# USB-PS2_1.net
KiCad netlist of a schematic drawn in Altium Designer
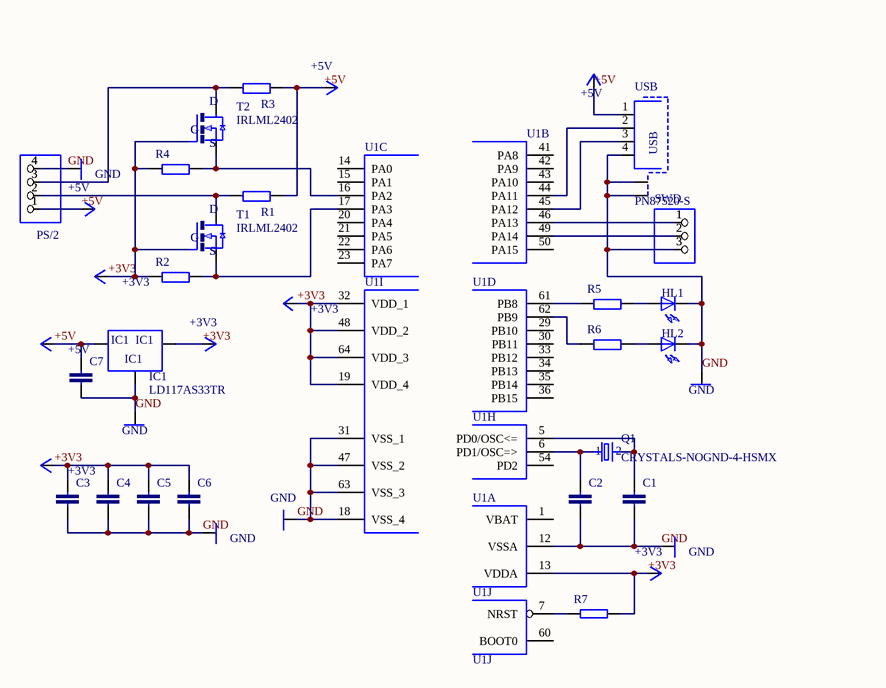
[diagram p0: USB-PS2_1.SchDoc]

(export (version "E")
  (design (tool "Eeschema 10.0.6"))
  (components
    (comp (ref "+3V1") (value "+3V3") (libsource (lib "supply1") (part "+3V3")))
    (comp (ref "+3V2") (value "+3V3") (libsource (lib "supply1") (part "+3V3")))
    (comp (ref "+3V3") (value "+3V3") (libsource (lib "") (part "+3V3_1")))
    (comp (ref "+3V4") (value "+3V3") (libsource (lib "supply1") (part "+3V3")))
    (comp (ref "+3V5") (value "+3V3") (libsource (lib "supply1") (part "+3V3")))
    (comp (ref "C1") (value "~") (footprint "C0603K") (libsource (lib "rcl") (part "C-EUC0603K")))
    (comp (ref "C2") (value "~") (footprint "C0603K") (libsource (lib "rcl") (part "C-EUC0603K")))
    (comp (ref "C3") (value "~") (footprint "C0603K") (libsource (lib "rcl") (part "C-EUC0603K")))
    (comp (ref "C4") (value "~") (footprint "C0603K") (libsource (lib "rcl") (part "C-EUC0603K")))
    (comp (ref "C5") (value "~") (footprint "C0603K") (libsource (lib "rcl") (part "C-EUC0603K")))
    (comp (ref "C6") (value "~") (footprint "C0603K") (libsource (lib "rcl") (part "C-EUC0603K")))
    (comp (ref "C7") (value "~") (footprint "C0603K") (libsource (lib "rcl") (part "C-EUC0603K")))
    (comp (ref "GND1") (value "GND") (libsource (lib "supply1") (part "GND")))
    (comp (ref "GND3") (value "GND") (libsource (lib "") (part "GND_1")))
    (comp (ref "GND4") (value "GND") (libsource (lib "supply1") (part "GND")))
    (comp (ref "GND5") (value "GND") (libsource (lib "supply1") (part "GND")))
    (comp (ref "GND6") (value "GND") (libsource (lib "supply1") (part "GND")))
    (comp (ref "GND7") (value "GND") (libsource (lib "supply1") (part "GND")))
    (comp (ref "HL1") (value "~") (footprint "SML0805") (libsource (lib "led") (part "LEDSML0805")))
    (comp (ref "HL2") (value "~") (footprint "SML0805") (libsource (lib "led") (part "LEDSML0805")))
    (comp (ref "IC1")
      (value "LD117AS33TR")
      (footprint "SOT223")
      (libsource (lib "v-reg") (part "LD117AS33TR"))
    )
    (comp (ref "P+1") (value "+5V") (libsource (lib "") (part "+5V_1")))
    (comp (ref "P+2") (value "+5V") (libsource (lib "") (part "+5V_1")))
    (comp (ref "P+3") (value "+5V") (libsource (lib "") (part "+5V_1")))
    (comp (ref "P+4") (value "+5V") (libsource (lib "supply1") (part "+5V")))
    (comp (ref "PS/2") (value "~") (footprint "1X04") (libsource (lib "pinhead") (part "PINHD-1X4")))
    (comp (ref "Q1")
      (value "CRYSTALS-NOGND-4-HSMX")
      (footprint "HC49-4-HSMX")
      (libsource (lib "IQD-Frequency-Products") (part "CRYSTALS-NOGND-4-HSMX"))
    )
    (comp (ref "R1") (value "~") (footprint "R0603") (libsource (lib "") (part "R-EU_R0603_2")))
    (comp (ref "R2") (value "~") (footprint "R0603") (libsource (lib "rcl") (part "R-EU_R0603")))
    (comp (ref "R3") (value "~") (footprint "R0603") (libsource (lib "") (part "R-EU_R0603_2")))
    (comp (ref "R4") (value "~") (footprint "R0603") (libsource (lib "rcl") (part "R-EU_R0603")))
    (comp (ref "R5") (value "~") (footprint "R0603") (libsource (lib "rcl") (part "R-EU_R0603")))
    (comp (ref "R6") (value "~") (footprint "R0603") (libsource (lib "rcl") (part "R-EU_R0603")))
    (comp (ref "R7") (value "~") (footprint "R0603") (libsource (lib "") (part "R-EU_R0603_1")))
    (comp (ref "SWD") (value "~") (footprint "1X03") (libsource (lib "pinhead") (part "PINHD-1X3")))
    (comp (ref "T1")
      (value "IRLML2402")
      (footprint "MICRO3")
      (libsource (lib "transistor-power") (part "IRLML2402"))
    )
    (comp (ref "T2")
      (value "IRLML2402")
      (footprint "MICRO3")
      (libsource (lib "transistor-power") (part "IRLML2402"))
    )
    (comp (ref "U1") (value "~") (footprint "TQFP64") (libsource (lib "") (part "STM32F10XRXT6_2")))
    (comp (ref "USB")
      (value "PN87520-S")
      (footprint "PN87520-S")
      (libsource (lib "con-berg") (part "PN87520-S"))
    )
  )
  (nets
    (net (code "1") (name "/+3V3") (class "Default")
      (node (ref "+3V1") (pin "0") (pinfunction "+3V3_0") (pintype "passive"))
      (node (ref "+3V2") (pin "0") (pinfunction "+3V3_0") (pintype "passive"))
      (node (ref "+3V3") (pin "0") (pinfunction "+3V3_0") (pintype "passive"))
      (node (ref "+3V4") (pin "0") (pinfunction "+3V3_0") (pintype "passive"))
      (node (ref "+3V5") (pin "0") (pinfunction "+3V3_0") (pintype "passive"))
      (node (ref "C3") (pin "1") (pinfunction "1_1") (pintype "passive"))
      (node (ref "C4") (pin "1") (pinfunction "1_1") (pintype "passive"))
      (node (ref "C5") (pin "1") (pinfunction "1_1") (pintype "passive"))
      (node (ref "C6") (pin "1") (pinfunction "1_1") (pintype "passive"))
      (node (ref "IC1") (pin "4") (pinfunction "OUT_4") (pintype "passive"))
      (node (ref "R2") (pin "1") (pinfunction "1_1") (pintype "passive"))
      (node (ref "R4") (pin "1") (pinfunction "1_1") (pintype "passive"))
      (node (ref "R7") (pin "2") (pinfunction "2_2") (pintype "passive"))
      (node (ref "T1") (pin "1") (pinfunction "G_1") (pintype "passive"))
      (node (ref "T2") (pin "1") (pinfunction "G_1") (pintype "passive"))
      (node (ref "U1") (pin "13") (pinfunction "VDDA_13") (pintype "passive"))
      (node (ref "U1") (pin "19") (pinfunction "VDD_4_19") (pintype "passive"))
      (node (ref "U1") (pin "32") (pinfunction "VDD_1_32") (pintype "passive"))
      (node (ref "U1") (pin "48") (pinfunction "VDD_2_48") (pintype "passive"))
      (node (ref "U1") (pin "64") (pinfunction "VDD_3_64") (pintype "passive"))
    )
    (net (code "2") (name "/+5V") (class "Default")
      (node (ref "C7") (pin "1") (pinfunction "1_1") (pintype "passive"))
      (node (ref "IC1") (pin "3") (pinfunction "IN_3") (pintype "passive"))
      (node (ref "P+1") (pin "0") (pinfunction "+5V_0") (pintype "passive"))
      (node (ref "P+2") (pin "0") (pinfunction "+5V_0") (pintype "passive"))
      (node (ref "P+3") (pin "0") (pinfunction "+5V_0") (pintype "passive"))
      (node (ref "P+4") (pin "0") (pinfunction "+5V_0") (pintype "passive"))
      (node (ref "PS/2") (pin "1") (pinfunction "1_1") (pintype "passive"))
      (node (ref "R1") (pin "1") (pinfunction "1_1") (pintype "passive"))
      (node (ref "R3") (pin "1") (pinfunction "1_1") (pintype "passive"))
      (node (ref "USB") (pin "1") (pinfunction "1_1") (pintype "passive"))
    )
    (net (code "3") (name "/GND") (class "Default")
      (node (ref "C1") (pin "2") (pinfunction "2_2") (pintype "passive"))
      (node (ref "C2") (pin "2") (pinfunction "2_2") (pintype "passive"))
      (node (ref "C3") (pin "2") (pinfunction "2_2") (pintype "passive"))
      (node (ref "C4") (pin "2") (pinfunction "2_2") (pintype "passive"))
      (node (ref "C5") (pin "2") (pinfunction "2_2") (pintype "passive"))
      (node (ref "C6") (pin "2") (pinfunction "2_2") (pintype "passive"))
      (node (ref "C7") (pin "2") (pinfunction "2_2") (pintype "passive"))
      (node (ref "GND1") (pin "0") (pinfunction "GND_0") (pintype "passive"))
      (node (ref "GND3") (pin "0") (pinfunction "GND_0") (pintype "passive"))
      (node (ref "GND4") (pin "0") (pinfunction "GND_0") (pintype "passive"))
      (node (ref "GND5") (pin "0") (pinfunction "GND_0") (pintype "passive"))
      (node (ref "GND6") (pin "0") (pinfunction "GND_0") (pintype "passive"))
      (node (ref "GND7") (pin "0") (pinfunction "GND_0") (pintype "passive"))
      (node (ref "HL1") (pin "C") (pinfunction "C_C") (pintype "passive"))
      (node (ref "HL2") (pin "C") (pinfunction "C_C") (pintype "passive"))
      (node (ref "IC1") (pin "1") (pinfunction "ADJ_1") (pintype "passive"))
      (node (ref "PS/2") (pin "4") (pinfunction "4_4") (pintype "passive"))
      (node (ref "SWD") (pin "3") (pinfunction "3_3") (pintype "passive"))
      (node (ref "U1") (pin "12") (pinfunction "VSSA_12") (pintype "passive"))
      (node (ref "U1") (pin "18") (pinfunction "VSS_4_18") (pintype "passive"))
      (node (ref "U1") (pin "31") (pinfunction "VSS_1_31") (pintype "passive"))
      (node (ref "U1") (pin "47") (pinfunction "VSS_2_47") (pintype "passive"))
      (node (ref "U1") (pin "63") (pinfunction "VSS_3_63") (pintype "passive"))
      (node (ref "USB") (pin "4") (pinfunction "4_4") (pintype "passive"))
      (node (ref "USB") (pin "S1") (pinfunction "S1_S1") (pintype "passive"))
      (node (ref "USB") (pin "S2") (pinfunction "S2_S2") (pintype "passive"))
    )
    (net (code "4") (name "Net-(HL1-PadA)") (class "Default")
      (node (ref "HL1") (pin "A") (pinfunction "A_A") (pintype "passive"))
      (node (ref "R5") (pin "2") (pinfunction "2_2") (pintype "passive"))
    )
    (net (code "5") (name "Net-(HL2-PadA)") (class "Default")
      (node (ref "HL2") (pin "A") (pinfunction "A_A") (pintype "passive"))
      (node (ref "R6") (pin "2") (pinfunction "2_2") (pintype "passive"))
    )
    (net (code "6") (name "Net-(T1-D)") (class "Default")
      (node (ref "PS/2") (pin "2") (pinfunction "2_2") (pintype "passive"))
      (node (ref "R1") (pin "2") (pinfunction "2_2") (pintype "passive"))
      (node (ref "T1") (pin "3") (pinfunction "D_3") (pintype "passive"))
    )
    (net (code "7") (name "Net-(T1-S)") (class "Default")
      (node (ref "R2") (pin "2") (pinfunction "2_2") (pintype "passive"))
      (node (ref "T1") (pin "2") (pinfunction "S_2") (pintype "passive"))
      (node (ref "U1") (pin "17") (pinfunction "PA3_17") (pintype "passive"))
    )
    (net (code "8") (name "Net-(T2-D)") (class "Default")
      (node (ref "PS/2") (pin "3") (pinfunction "3_3") (pintype "passive"))
      (node (ref "R3") (pin "2") (pinfunction "2_2") (pintype "passive"))
      (node (ref "T2") (pin "3") (pinfunction "D_3") (pintype "passive"))
    )
    (net (code "9") (name "Net-(T2-S)") (class "Default")
      (node (ref "R4") (pin "2") (pinfunction "2_2") (pintype "passive"))
      (node (ref "T2") (pin "2") (pinfunction "S_2") (pintype "passive"))
      (node (ref "U1") (pin "16") (pinfunction "PA2_16") (pintype "passive"))
    )
    (net (code "10") (name "Net-(U1B-PA11)") (class "Default")
      (node (ref "U1") (pin "44") (pinfunction "PA11_44") (pintype "passive"))
      (node (ref "USB") (pin "2") (pinfunction "2_2") (pintype "passive"))
    )
    (net (code "11") (name "Net-(U1B-PA12)") (class "Default")
      (node (ref "U1") (pin "45") (pinfunction "PA12_45") (pintype "passive"))
      (node (ref "USB") (pin "3") (pinfunction "3_3") (pintype "passive"))
    )
    (net (code "12") (name "Net-(U1B-PA13)") (class "Default")
      (node (ref "SWD") (pin "1") (pinfunction "1_1") (pintype "passive"))
      (node (ref "U1") (pin "46") (pinfunction "PA13_46") (pintype "passive"))
    )
    (net (code "13") (name "Net-(U1B-PA14)") (class "Default")
      (node (ref "SWD") (pin "2") (pinfunction "2_2") (pintype "passive"))
      (node (ref "U1") (pin "49") (pinfunction "PA14_49") (pintype "passive"))
    )
    (net (code "14") (name "Net-(U1D-PB8)") (class "Default")
      (node (ref "R5") (pin "1") (pinfunction "1_1") (pintype "passive"))
      (node (ref "U1") (pin "61") (pinfunction "PB8_61") (pintype "passive"))
    )
    (net (code "15") (name "Net-(U1D-PB9)") (class "Default")
      (node (ref "R6") (pin "1") (pinfunction "1_1") (pintype "passive"))
      (node (ref "U1") (pin "62") (pinfunction "PB9_62") (pintype "passive"))
    )
    (net (code "16") (name "Net-(U1H-PD0{slash}OSC<=)") (class "Default")
      (node (ref "C1") (pin "1") (pinfunction "1_1") (pintype "passive"))
      (node (ref "Q1") (pin "2") (pinfunction "2_2") (pintype "passive"))
      (node (ref "U1") (pin "5") (pinfunction "PD0/OSC<=_5") (pintype "passive"))
    )
    (net (code "17") (name "Net-(U1H-PD1{slash}OSC=>)") (class "Default")
      (node (ref "C2") (pin "1") (pinfunction "1_1") (pintype "passive"))
      (node (ref "Q1") (pin "1") (pinfunction "1_1") (pintype "passive"))
      (node (ref "U1") (pin "6") (pinfunction "PD1/OSC=>_6") (pintype "passive"))
    )
    (net (code "18") (name "Net-(U1J-NRST)") (class "Default")
      (node (ref "R7") (pin "1") (pinfunction "1_1") (pintype "passive"))
      (node (ref "U1") (pin "7") (pinfunction "NRST_7") (pintype "passive"))
    )
    (net (code "19") (name "unconnected-(U1A-VBAT-Pad1)") (class "Default")
      (node (ref "U1") (pin "1") (pinfunction "VBAT_1") (pintype "passive"))
    )
    (net (code "20") (name "unconnected-(U1B-PA8-Pad41)") (class "Default")
      (node (ref "U1") (pin "41") (pinfunction "PA8_41") (pintype "passive"))
    )
    (net (code "21") (name "unconnected-(U1B-PA9-Pad42)") (class "Default")
      (node (ref "U1") (pin "42") (pinfunction "PA9_42") (pintype "passive"))
    )
    (net (code "22") (name "unconnected-(U1B-PA10-Pad43)") (class "Default")
      (node (ref "U1") (pin "43") (pinfunction "PA10_43") (pintype "passive"))
    )
    (net (code "23") (name "unconnected-(U1B-PA15-Pad50)") (class "Default")
      (node (ref "U1") (pin "50") (pinfunction "PA15_50") (pintype "passive"))
    )
    (net (code "24") (name "unconnected-(U1C-PA0-Pad14)") (class "Default")
      (node (ref "U1") (pin "14") (pinfunction "PA0_14") (pintype "passive"))
    )
    (net (code "25") (name "unconnected-(U1C-PA1-Pad15)") (class "Default")
      (node (ref "U1") (pin "15") (pinfunction "PA1_15") (pintype "passive"))
    )
    (net (code "26") (name "unconnected-(U1C-PA4-Pad20)") (class "Default")
      (node (ref "U1") (pin "20") (pinfunction "PA4_20") (pintype "passive"))
    )
    (net (code "27") (name "unconnected-(U1C-PA5-Pad21)") (class "Default")
      (node (ref "U1") (pin "21") (pinfunction "PA5_21") (pintype "passive"))
    )
    (net (code "28") (name "unconnected-(U1C-PA6-Pad22)") (class "Default")
      (node (ref "U1") (pin "22") (pinfunction "PA6_22") (pintype "passive"))
    )
    (net (code "29") (name "unconnected-(U1C-PA7-Pad23)") (class "Default")
      (node (ref "U1") (pin "23") (pinfunction "PA7_23") (pintype "passive"))
    )
    (net (code "30") (name "unconnected-(U1D-PB10-Pad29)") (class "Default")
      (node (ref "U1") (pin "29") (pinfunction "PB10_29") (pintype "passive"))
    )
    (net (code "31") (name "unconnected-(U1D-PB11-Pad30)") (class "Default")
      (node (ref "U1") (pin "30") (pinfunction "PB11_30") (pintype "passive"))
    )
    (net (code "32") (name "unconnected-(U1D-PB12-Pad33)") (class "Default")
      (node (ref "U1") (pin "33") (pinfunction "PB12_33") (pintype "passive"))
    )
    (net (code "33") (name "unconnected-(U1D-PB13-Pad34)") (class "Default")
      (node (ref "U1") (pin "34") (pinfunction "PB13_34") (pintype "passive"))
    )
    (net (code "34") (name "unconnected-(U1D-PB14-Pad35)") (class "Default")
      (node (ref "U1") (pin "35") (pinfunction "PB14_35") (pintype "passive"))
    )
    (net (code "35") (name "unconnected-(U1D-PB15-Pad36)") (class "Default")
      (node (ref "U1") (pin "36") (pinfunction "PB15_36") (pintype "passive"))
    )
    (net (code "36") (name "unconnected-(U1H-PD2-Pad54)") (class "Default")
      (node (ref "U1") (pin "54") (pinfunction "PD2_54") (pintype "passive"))
    )
    (net (code "37") (name "unconnected-(U1J-BOOT0-Pad60)") (class "Default")
      (node (ref "U1") (pin "60") (pinfunction "BOOT0_60") (pintype "passive"))
    )
  )
)
